# GPS-Board.net
KiCad netlist of a schematic drawn in Altium Designer
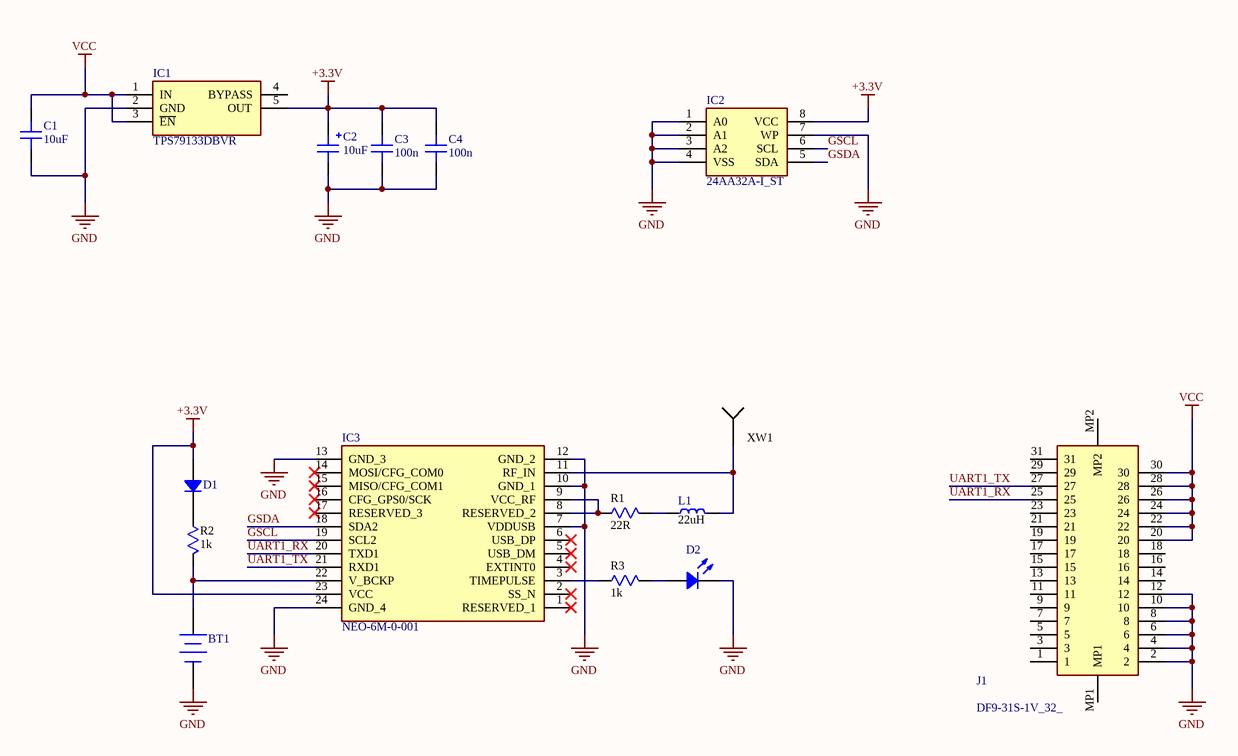
[diagram p0: GPS-Board.SchDoc]

(export (version "E")
  (design (tool "Eeschema 10.0.6"))
  (components
    (comp (ref "BT1")
      (value "MS621FE-FL11E")
      (footprint "SEIK-MS621FE-FL11E-2_V")
      (description "MS Lihium Rechargeable Battery, 3 V, -20 to 60 degC, Tray")
      (fields (field (name "MANUFACTURER") "SeikoInstruments"))
      (libsource (lib "Altium Content Vault") (part "BATTERY_SINGLE-2"))
    )
    (comp (ref "C1")
      (value "10uF")
      (footprint "PcbLib:CAP: 0805")
      (description "SMD Capacitor")
      (libsource (lib "Schlib") (part "Capacitor"))
    )
    (comp (ref "C2")
      (value "10uF")
      (footprint "PcbLib:CAP: TANTAL-A")
      (description "SMD Capacitor Polar")
      (libsource (lib "Schlib") (part "Capacitor_polar"))
    )
    (comp (ref "C3")
      (value "100n")
      (footprint "PcbLib:CAP: 0603")
      (description "SMD Capacitor")
      (libsource (lib "Schlib") (part "Capacitor"))
    )
    (comp (ref "C4")
      (value "100n")
      (footprint "PcbLib:CAP: 0603")
      (description "SMD Capacitor")
      (libsource (lib "Schlib") (part "Capacitor"))
    )
    (comp (ref "D1")
      (value "~")
      (footprint "PcbLib:DIODE: SOD323")
      (description "Rectifier Diode")
      (libsource (lib "Schlib") (part "Diode"))
    )
    (comp (ref "D2")
      (value "~")
      (footprint "PcbLib:LED0805")
      (description "Chip LED")
      (libsource (lib "Schlib") (part "LED"))
    )
    (comp (ref "IC1")
      (value "TPS79133DBVR")
      (footprint "PcbLib:SOT95P280X145-5N")
      (description "Integrated Circuit")
      (fields (field (name "MOUSER PART NUMBER") "595-TPS79133DBVR"))
      (libsource (lib "*") (part "TPS79133DBVR"))
    )
    (comp (ref "IC2")
      (value "24AA32A-I_ST")
      (footprint "PcbLib:SOP65P640X120-8N")
      (description "Integrated Circuit")
      (fields
        (field (name "MANUFACTURER_PART_NUMBER") "24AA32A-I/ST")
        (field (name "MOUSER PART NUMBER") "579-24AA32A-I/ST")
      )
      (libsource (lib "*") (part "24AA32A-I_ST"))
    )
    (comp (ref "IC3")
      (value "NEO-6M-0-001")
      (footprint "PcbLib:NEO6M0001")
      (description "Integrated Circuit")
      (libsource (lib "*") (part "NEO-6M-0-001"))
    )
    (comp (ref "J1")
      (value "DF9-31S-1V_32_")
      (footprint "PcbLib:DF931S1V32")
      (description "Connector")
      (fields
        (field (name "MANUFACTURER_PART_NUMBER") "DF9-31S-1V(32)")
        (field (name "MOUSER PART NUMBER") "798-DF9-31S-1V32")
      )
      (libsource (lib "Schlib") (part "DF9-31S-1V_32_"))
    )
    (comp (ref "L1")
      (value "22uH")
      (footprint "PcbLib:IND: 0805")
      (description "INDUCTOR, SMD")
      (libsource (lib "Schlib") (part "IND_SMD"))
    )
    (comp (ref "R1")
      (value "22R")
      (footprint "PcbLib:RES: 0603")
      (fields
        (field (name "MANUFACTURER") "Yageo")
        (field (name "PARTNUMBER") "RC0201JR-07100RL")
        (field (name "VALUEMANUFACTURERPARTNUMBER") "Resistor film, 22R, , 0201, 0.05W, -55...+125°C")
      )
      (libsource (lib "Schlib") (part "Resistor"))
    )
    (comp (ref "R2")
      (value "1k")
      (footprint "PcbLib:RES: 0603")
      (fields
        (field (name "MANUFACTURER") "Yageo")
        (field (name "PARTNUMBER") "RC0201JR-07100RL")
        (field (name "VALUEMANUFACTURERPARTNUMBER") "Resistor film, 1k, , 0201, 0.05W, -55...+125°C")
      )
      (libsource (lib "Schlib") (part "Resistor"))
    )
    (comp (ref "R3")
      (value "1k")
      (footprint "PcbLib:RES: 0603")
      (fields
        (field (name "MANUFACTURER") "Yageo")
        (field (name "PARTNUMBER") "RC0201JR-07100RL")
        (field (name "VALUEMANUFACTURERPARTNUMBER") "Resistor film, 1k, , 0201, 0.05W, -55...+125°C")
      )
      (libsource (lib "Schlib") (part "Resistor"))
    )
    (comp (ref "XW1")
      (value "~")
      (footprint "PcbLib:ANT: PCB")
      (libsource (lib "Schlib") (part "Connector RF"))
    )
  )
  (nets
    (net (code "1") (name "+3.3V") (class "Default")
      (node (ref "C2") (pin "1") (pinfunction "1_1") (pintype "passive"))
      (node (ref "C3") (pin "2") (pinfunction "2_2") (pintype "passive"))
      (node (ref "C4") (pin "2") (pinfunction "2_2") (pintype "passive"))
      (node (ref "D1") (pin "1") (pinfunction "1_1") (pintype "passive"))
      (node (ref "IC1") (pin "5") (pinfunction "OUT_5") (pintype "passive"))
      (node (ref "IC2") (pin "8") (pinfunction "VCC_8") (pintype "passive"))
      (node (ref "IC3") (pin "23") (pinfunction "VCC_23") (pintype "passive"))
    )
    (net (code "2") (name "/GSCL") (class "Default")
      (node (ref "IC2") (pin "6") (pinfunction "SCL_6") (pintype "passive"))
      (node (ref "IC3") (pin "19") (pinfunction "SCL2_19") (pintype "passive"))
    )
    (net (code "3") (name "/GSDA") (class "Default")
      (node (ref "IC2") (pin "5") (pinfunction "SDA_5") (pintype "passive"))
      (node (ref "IC3") (pin "18") (pinfunction "SDA2_18") (pintype "passive"))
    )
    (net (code "4") (name "/UART1_RX") (class "Default")
      (node (ref "IC3") (pin "20") (pinfunction "TXD1_20") (pintype "passive"))
      (node (ref "J1") (pin "25") (pinfunction "25_25") (pintype "passive"))
    )
    (net (code "5") (name "/UART1_TX") (class "Default")
      (node (ref "IC3") (pin "21") (pinfunction "RXD1_21") (pintype "passive"))
      (node (ref "J1") (pin "27") (pinfunction "27_27") (pintype "passive"))
    )
    (net (code "6") (name "GND") (class "Default")
      (node (ref "BT1") (pin "2") (pinfunction "-_2") (pintype "passive"))
      (node (ref "C1") (pin "1") (pinfunction "1_1") (pintype "passive"))
      (node (ref "C2") (pin "2") (pinfunction "2_2") (pintype "passive"))
      (node (ref "C3") (pin "1") (pinfunction "1_1") (pintype "passive"))
      (node (ref "C4") (pin "1") (pinfunction "1_1") (pintype "passive"))
      (node (ref "D2") (pin "2") (pinfunction "2_2") (pintype "passive"))
      (node (ref "IC1") (pin "2") (pinfunction "GND_2") (pintype "passive"))
      (node (ref "IC2") (pin "1") (pinfunction "A0_1") (pintype "passive"))
      (node (ref "IC2") (pin "2") (pinfunction "A1_2") (pintype "passive"))
      (node (ref "IC2") (pin "3") (pinfunction "A2_3") (pintype "passive"))
      (node (ref "IC2") (pin "4") (pinfunction "VSS_4") (pintype "passive"))
      (node (ref "IC2") (pin "7") (pinfunction "WP_7") (pintype "passive"))
      (node (ref "IC3") (pin "10") (pinfunction "GND_1_10") (pintype "passive"))
      (node (ref "IC3") (pin "12") (pinfunction "GND_2_12") (pintype "passive"))
      (node (ref "IC3") (pin "13") (pinfunction "GND_3_13") (pintype "passive"))
      (node (ref "IC3") (pin "24") (pinfunction "GND_4_24") (pintype "passive"))
      (node (ref "IC3") (pin "7") (pinfunction "VDDUSB_7") (pintype "passive"))
      (node (ref "J1") (pin "10") (pinfunction "10_10") (pintype "passive"))
      (node (ref "J1") (pin "12") (pinfunction "12_12") (pintype "passive"))
      (node (ref "J1") (pin "2") (pinfunction "2_2") (pintype "passive"))
      (node (ref "J1") (pin "4") (pinfunction "4_4") (pintype "passive"))
      (node (ref "J1") (pin "6") (pinfunction "6_6") (pintype "passive"))
      (node (ref "J1") (pin "8") (pinfunction "8_8") (pintype "passive"))
    )
    (net (code "7") (name "Net-(BT1-+)") (class "Default")
      (node (ref "BT1") (pin "1") (pinfunction "+_1") (pintype "passive"))
      (node (ref "IC3") (pin "22") (pinfunction "V_BCKP_22") (pintype "passive"))
      (node (ref "R2") (pin "2") (pinfunction "2_2") (pintype "passive"))
    )
    (net (code "8") (name "Net-(D1-Pad2)") (class "Default")
      (node (ref "D1") (pin "2") (pinfunction "2_2") (pintype "passive"))
      (node (ref "R2") (pin "1") (pinfunction "1_1") (pintype "passive"))
    )
    (net (code "9") (name "Net-(D2-Pad1)") (class "Default")
      (node (ref "D2") (pin "1") (pinfunction "1_1") (pintype "passive"))
      (node (ref "R3") (pin "2") (pinfunction "2_2") (pintype "passive"))
    )
    (net (code "10") (name "Net-(IC3-RESERVED_2)") (class "Default")
      (node (ref "IC3") (pin "8") (pinfunction "RESERVED_2_8") (pintype "passive"))
      (node (ref "IC3") (pin "9") (pinfunction "VCC_RF_9") (pintype "passive"))
      (node (ref "R1") (pin "1") (pinfunction "1_1") (pintype "passive"))
    )
    (net (code "11") (name "Net-(IC3-RF_IN)") (class "Default")
      (node (ref "IC3") (pin "11") (pinfunction "RF_IN_11") (pintype "passive"))
      (node (ref "L1") (pin "2") (pinfunction "2_2") (pintype "passive"))
      (node (ref "XW1") (pin "1") (pinfunction "SIG_1") (pintype "passive"))
    )
    (net (code "12") (name "Net-(IC3-TIMEPULSE)") (class "Default")
      (node (ref "IC3") (pin "3") (pinfunction "TIMEPULSE_3") (pintype "passive"))
      (node (ref "R3") (pin "1") (pinfunction "1_1") (pintype "passive"))
    )
    (net (code "13") (name "Net-(L1-Pad1)") (class "Default")
      (node (ref "L1") (pin "1") (pinfunction "1_1") (pintype "passive"))
      (node (ref "R1") (pin "2") (pinfunction "2_2") (pintype "passive"))
    )
    (net (code "14") (name "VCC") (class "Default")
      (node (ref "C1") (pin "2") (pinfunction "2_2") (pintype "passive"))
      (node (ref "IC1") (pin "1") (pinfunction "IN_1") (pintype "passive"))
      (node (ref "IC1") (pin "3") (pinfunction "~{EN}_3") (pintype "passive"))
      (node (ref "J1") (pin "20") (pinfunction "20_20") (pintype "passive"))
      (node (ref "J1") (pin "22") (pinfunction "22_22") (pintype "passive"))
      (node (ref "J1") (pin "24") (pinfunction "24_24") (pintype "passive"))
      (node (ref "J1") (pin "26") (pinfunction "26_26") (pintype "passive"))
      (node (ref "J1") (pin "28") (pinfunction "28_28") (pintype "passive"))
      (node (ref "J1") (pin "30") (pinfunction "30_30") (pintype "passive"))
    )
    (net (code "15") (name "unconnected-(IC1-BYPASS-Pad4)") (class "Default")
      (node (ref "IC1") (pin "4") (pinfunction "BYPASS_4") (pintype "passive"))
    )
    (net (code "16") (name "unconnected-(IC3-CFG_GPS0{slash}SCK-Pad16)") (class "Default")
      (node (ref "IC3") (pin "16") (pinfunction "CFG_GPS0/SCK_16") (pintype "passive+no_connect"))
    )
    (net (code "17") (name "unconnected-(IC3-EXTINT0-Pad4)") (class "Default")
      (node (ref "IC3") (pin "4") (pinfunction "EXTINT0_4") (pintype "passive+no_connect"))
    )
    (net (code "18") (name "unconnected-(IC3-MISO{slash}CFG_COM1-Pad15)") (class "Default")
      (node (ref "IC3") (pin "15") (pinfunction "MISO/CFG_COM1_15") (pintype "passive+no_connect"))
    )
    (net (code "19") (name "unconnected-(IC3-MOSI{slash}CFG_COM0-Pad14)") (class "Default")
      (node (ref "IC3") (pin "14") (pinfunction "MOSI/CFG_COM0_14") (pintype "passive+no_connect"))
    )
    (net (code "20") (name "unconnected-(IC3-RESERVED_1-Pad1)") (class "Default")
      (node (ref "IC3") (pin "1") (pinfunction "RESERVED_1_1") (pintype "passive+no_connect"))
    )
    (net (code "21") (name "unconnected-(IC3-RESERVED_3-Pad17)") (class "Default")
      (node (ref "IC3") (pin "17") (pinfunction "RESERVED_3_17") (pintype "passive+no_connect"))
    )
    (net (code "22") (name "unconnected-(IC3-SS_N-Pad2)") (class "Default")
      (node (ref "IC3") (pin "2") (pinfunction "SS_N_2") (pintype "passive+no_connect"))
    )
    (net (code "23") (name "unconnected-(IC3-USB_DM-Pad5)") (class "Default")
      (node (ref "IC3") (pin "5") (pinfunction "USB_DM_5") (pintype "passive+no_connect"))
    )
    (net (code "24") (name "unconnected-(IC3-USB_DP-Pad6)") (class "Default")
      (node (ref "IC3") (pin "6") (pinfunction "USB_DP_6") (pintype "passive+no_connect"))
    )
    (net (code "25") (name "unconnected-(J1-Pad1)") (class "Default")
      (node (ref "J1") (pin "1") (pinfunction "1_1") (pintype "passive"))
    )
    (net (code "26") (name "unconnected-(J1-Pad3)") (class "Default")
      (node (ref "J1") (pin "3") (pinfunction "3_3") (pintype "passive"))
    )
    (net (code "27") (name "unconnected-(J1-Pad5)") (class "Default")
      (node (ref "J1") (pin "5") (pinfunction "5_5") (pintype "passive"))
    )
    (net (code "28") (name "unconnected-(J1-Pad7)") (class "Default")
      (node (ref "J1") (pin "7") (pinfunction "7_7") (pintype "passive"))
    )
    (net (code "29") (name "unconnected-(J1-Pad9)") (class "Default")
      (node (ref "J1") (pin "9") (pinfunction "9_9") (pintype "passive"))
    )
    (net (code "30") (name "unconnected-(J1-Pad11)") (class "Default")
      (node (ref "J1") (pin "11") (pinfunction "11_11") (pintype "passive"))
    )
    (net (code "31") (name "unconnected-(J1-Pad13)") (class "Default")
      (node (ref "J1") (pin "13") (pinfunction "13_13") (pintype "passive"))
    )
    (net (code "32") (name "unconnected-(J1-Pad14)") (class "Default")
      (node (ref "J1") (pin "14") (pinfunction "14_14") (pintype "passive"))
    )
    (net (code "33") (name "unconnected-(J1-Pad15)") (class "Default")
      (node (ref "J1") (pin "15") (pinfunction "15_15") (pintype "passive"))
    )
    (net (code "34") (name "unconnected-(J1-Pad16)") (class "Default")
      (node (ref "J1") (pin "16") (pinfunction "16_16") (pintype "passive"))
    )
    (net (code "35") (name "unconnected-(J1-Pad17)") (class "Default")
      (node (ref "J1") (pin "17") (pinfunction "17_17") (pintype "passive"))
    )
    (net (code "36") (name "unconnected-(J1-Pad18)") (class "Default")
      (node (ref "J1") (pin "18") (pinfunction "18_18") (pintype "passive"))
    )
    (net (code "37") (name "unconnected-(J1-Pad19)") (class "Default")
      (node (ref "J1") (pin "19") (pinfunction "19_19") (pintype "passive"))
    )
    (net (code "38") (name "unconnected-(J1-Pad21)") (class "Default")
      (node (ref "J1") (pin "21") (pinfunction "21_21") (pintype "passive"))
    )
    (net (code "39") (name "unconnected-(J1-Pad23)") (class "Default")
      (node (ref "J1") (pin "23") (pinfunction "23_23") (pintype "passive"))
    )
    (net (code "40") (name "unconnected-(J1-Pad29)") (class "Default")
      (node (ref "J1") (pin "29") (pinfunction "29_29") (pintype "passive"))
    )
    (net (code "41") (name "unconnected-(J1-Pad31)") (class "Default")
      (node (ref "J1") (pin "31") (pinfunction "31_31") (pintype "passive"))
    )
    (net (code "42") (name "unconnected-(J1-PadMP1)") (class "Default")
      (node (ref "J1") (pin "MP1") (pinfunction "MP1_MP1") (pintype "passive"))
    )
    (net (code "43") (name "unconnected-(J1-PadMP2)") (class "Default")
      (node (ref "J1") (pin "MP2") (pinfunction "MP2_MP2") (pintype "passive"))
    )
  )
)
